# Oscilador.net
KiCad netlist of a schematic drawn in Altium Designer
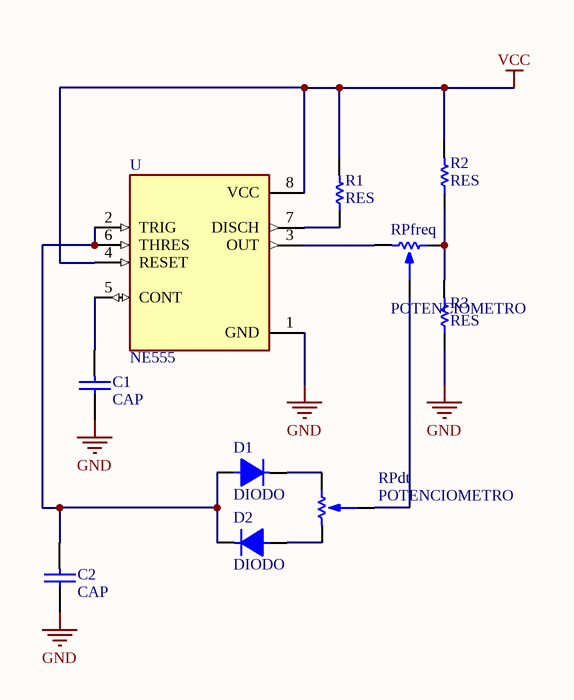
[diagram p0: Oscilador.SchDoc]

(export (version "E")
  (design (tool "Eeschema 10.0.6"))
  (components
    (comp (ref "C1") (value "CAP") (footprint "CAP200") (libsource (lib "LIBEBAL") (part "CAP")))
    (comp (ref "C2") (value "CAP") (footprint "CAP200") (libsource (lib "LIBEBAL") (part "CAP")))
    (comp (ref "D1") (value "DIODO") (footprint "DO41") (libsource (lib "LIBEBAL") (part "DIODO")))
    (comp (ref "D2") (value "DIODO") (footprint "DO41") (libsource (lib "LIBEBAL") (part "DIODO")))
    (comp (ref "R1") (value "RES") (footprint "RES400") (libsource (lib "LIBEBAL") (part "RES")))
    (comp (ref "R2") (value "RES") (footprint "RES400") (libsource (lib "LIBEBAL") (part "RES")))
    (comp (ref "R3") (value "RES") (footprint "RES400") (libsource (lib "LIBEBAL") (part "RES")))
    (comp (ref "RPdt")
      (value "POTENCIOMETRO")
      (footprint "POTENCIOMETRO")
      (libsource (lib "LIBEBAL") (part "POTENCIOMETRO"))
    )
    (comp (ref "RPfreq")
      (value "POTENCIOMETRO")
      (footprint "POTENCIOMETRO")
      (libsource (lib "LIBEBAL") (part "POTENCIOMETRO"))
    )
    (comp (ref "U")
      (value "NE555")
      (footprint "DIP794W45P254L1060H508Q8")
      (description "555 Type, Timer/Oscillator _Single_ IC 100kHz 8-SOIC")
      (fields (field (name "MF") "Texas Instruments"))
      (libsource (lib "NE555") (part "NE555"))
    )
  )
  (nets
    (net (code "1") (name "GND") (class "Default")
      (node (ref "C1") (pin "2") (pinfunction "2_2") (pintype "passive"))
      (node (ref "C2") (pin "2") (pinfunction "2_2") (pintype "passive"))
      (node (ref "R3") (pin "1") (pinfunction "1_1") (pintype "passive"))
      (node (ref "U") (pin "1") (pinfunction "GND_1") (pintype "power_in"))
    )
    (net (code "2") (name "Net-(D1-Pad2)") (class "Default")
      (node (ref "D1") (pin "2") (pinfunction "2_2") (pintype "passive"))
      (node (ref "RPdt") (pin "1") (pinfunction "1_1") (pintype "passive"))
    )
    (net (code "3") (name "Net-(D2-Pad1)") (class "Default")
      (node (ref "D2") (pin "1") (pinfunction "1_1") (pintype "passive"))
      (node (ref "RPdt") (pin "3") (pinfunction "3_3") (pintype "passive"))
    )
    (net (code "4") (name "Net-(R2-Pad1)") (class "Default")
      (node (ref "R2") (pin "1") (pinfunction "1_1") (pintype "passive"))
      (node (ref "R3") (pin "2") (pinfunction "2_2") (pintype "passive"))
      (node (ref "RPfreq") (pin "1") (pinfunction "1_1") (pintype "passive"))
    )
    (net (code "5") (name "Net-(RPdt-Pad2)") (class "Default")
      (node (ref "RPdt") (pin "2") (pinfunction "2_2") (pintype "passive"))
      (node (ref "RPfreq") (pin "2") (pinfunction "2_2") (pintype "passive"))
    )
    (net (code "6") (name "Net-(U-CONT)") (class "Default")
      (node (ref "C1") (pin "1") (pinfunction "1_1") (pintype "passive"))
      (node (ref "U") (pin "5") (pinfunction "CONT_5") (pintype "bidirectional"))
    )
    (net (code "7") (name "Net-(U-DISCH)") (class "Default")
      (node (ref "R1") (pin "1") (pinfunction "1_1") (pintype "passive"))
      (node (ref "U") (pin "7") (pinfunction "DISCH_7") (pintype "output"))
    )
    (net (code "8") (name "Net-(U-OUT)") (class "Default")
      (node (ref "RPfreq") (pin "3") (pinfunction "3_3") (pintype "passive"))
      (node (ref "U") (pin "3") (pinfunction "OUT_3") (pintype "output"))
    )
    (net (code "9") (name "Net-(U-THRES)") (class "Default")
      (node (ref "C2") (pin "1") (pinfunction "1_1") (pintype "passive"))
      (node (ref "D1") (pin "1") (pinfunction "1_1") (pintype "passive"))
      (node (ref "D2") (pin "2") (pinfunction "2_2") (pintype "passive"))
      (node (ref "U") (pin "2") (pinfunction "TRIG_2") (pintype "input"))
      (node (ref "U") (pin "6") (pinfunction "THRES_6") (pintype "input"))
    )
    (net (code "10") (name "VCC") (class "Default")
      (node (ref "R1") (pin "2") (pinfunction "2_2") (pintype "passive"))
      (node (ref "R2") (pin "2") (pinfunction "2_2") (pintype "passive"))
      (node (ref "U") (pin "4") (pinfunction "RESET_4") (pintype "input"))
      (node (ref "U") (pin "8") (pinfunction "VCC_8") (pintype "power_in"))
    )
  )
)
